# Sheet3.net
KiCad netlist of a schematic drawn in Altium Designer
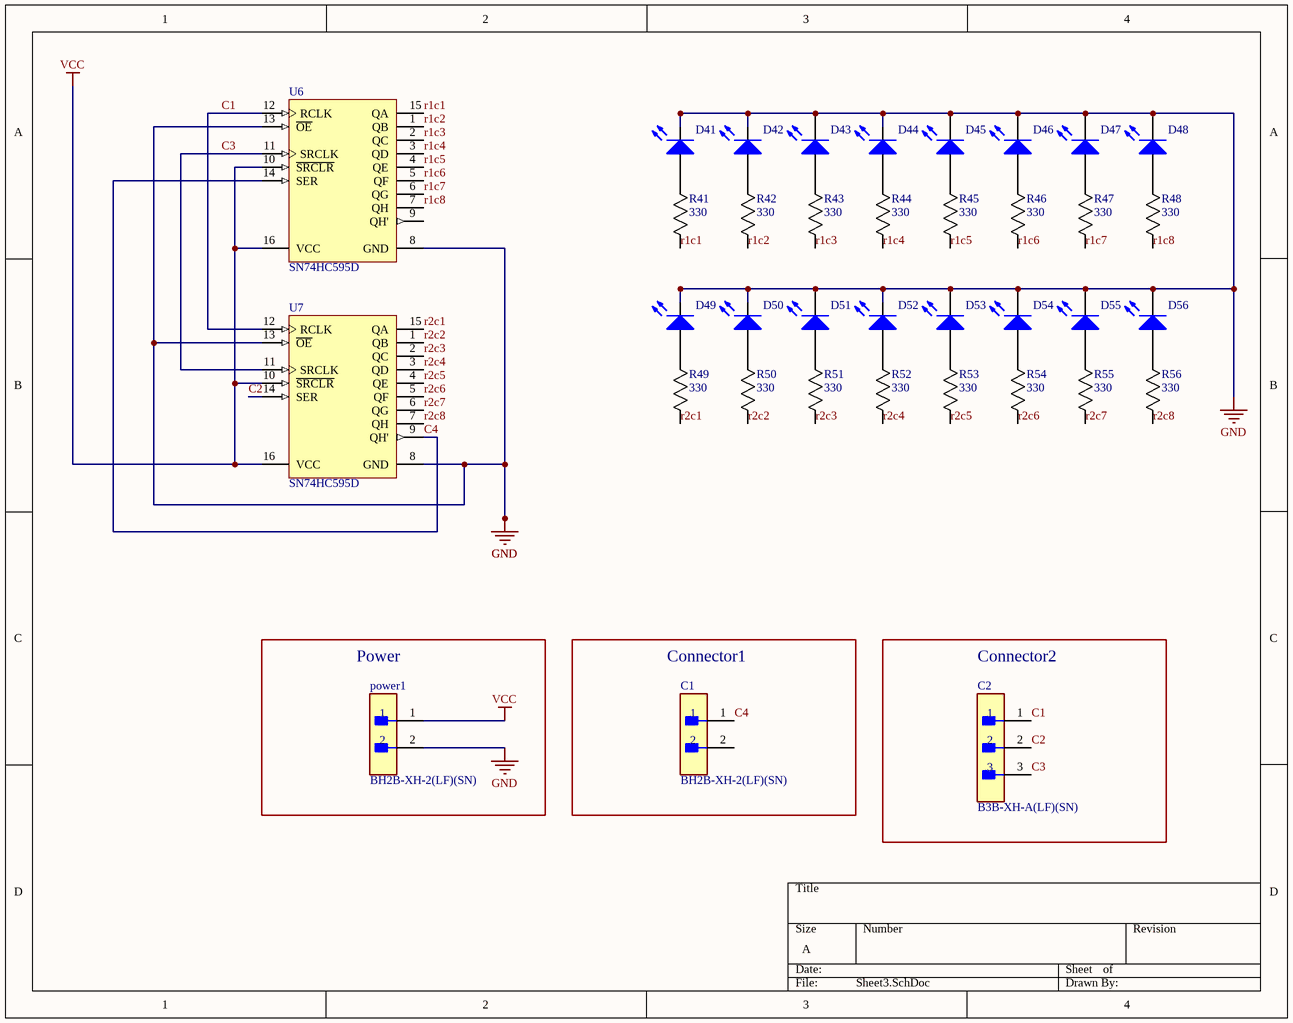
[diagram p0: Sheet3.SchDoc]

(export (version "E")
  (design (tool "Eeschema 10.0.6"))
  (components
    (comp (ref "C1")
      (value "BH2B-XH-2(LF)(SN)")
      (footprint "FP-BH2B-XH-2_LF_SN-MFG")
      (description "CONN HEADER VERT 2POS 2.5MM")
      (libsource (lib "Altium Content Vault") (part "3bc925449376181038e59eaffc5286c"))
    )
    (comp (ref "C2")
      (value "B3B-XH-A(LF)(SN)")
      (footprint "FP-B3B-XH-A_LF_SN-MFG")
      (description "CONN HEADER VERT 3POS 2.5MM")
      (libsource (lib "Altium Content Vault") (part "0d3f023dd272f625e17a2be33dea85f"))
    )
    (comp (ref "D41")
      (value "Light-Emitting Diode")
      (libsource (lib "Simulation Generic Components") (part "LED"))
    )
    (comp (ref "D42")
      (value "Light-Emitting Diode")
      (libsource (lib "Simulation Generic Components") (part "LED"))
    )
    (comp (ref "D43")
      (value "Light-Emitting Diode")
      (libsource (lib "Simulation Generic Components") (part "LED"))
    )
    (comp (ref "D44")
      (value "Light-Emitting Diode")
      (libsource (lib "Simulation Generic Components") (part "LED"))
    )
    (comp (ref "D45")
      (value "Light-Emitting Diode")
      (libsource (lib "Simulation Generic Components") (part "LED"))
    )
    (comp (ref "D46")
      (value "Light-Emitting Diode")
      (libsource (lib "Simulation Generic Components") (part "LED"))
    )
    (comp (ref "D47")
      (value "Light-Emitting Diode")
      (libsource (lib "Simulation Generic Components") (part "LED"))
    )
    (comp (ref "D48")
      (value "Light-Emitting Diode")
      (libsource (lib "Simulation Generic Components") (part "LED"))
    )
    (comp (ref "D49")
      (value "Light-Emitting Diode")
      (libsource (lib "Simulation Generic Components") (part "LED"))
    )
    (comp (ref "D50")
      (value "Light-Emitting Diode")
      (libsource (lib "Simulation Generic Components") (part "LED"))
    )
    (comp (ref "D51")
      (value "Light-Emitting Diode")
      (libsource (lib "Simulation Generic Components") (part "LED"))
    )
    (comp (ref "D52")
      (value "Light-Emitting Diode")
      (libsource (lib "Simulation Generic Components") (part "LED"))
    )
    (comp (ref "D53")
      (value "Light-Emitting Diode")
      (libsource (lib "Simulation Generic Components") (part "LED"))
    )
    (comp (ref "D54")
      (value "Light-Emitting Diode")
      (libsource (lib "Simulation Generic Components") (part "LED"))
    )
    (comp (ref "D55")
      (value "Light-Emitting Diode")
      (libsource (lib "Simulation Generic Components") (part "LED"))
    )
    (comp (ref "D56")
      (value "Light-Emitting Diode")
      (libsource (lib "Simulation Generic Components") (part "LED"))
    )
    (comp (ref "power1")
      (value "BH2B-XH-2(LF)(SN)")
      (footprint "FP-BH2B-XH-2_LF_SN-MFG")
      (description "CONN HEADER VERT 2POS 2.5MM")
      (libsource (lib "Altium Content Vault") (part "3bc925449376181038e59eaffc5286c"))
    )
    (comp (ref "R41")
      (value "330")
      (footprint "RES_AC03_VIS")
      (fields (field (name "TOLERANCE") "5%"))
      (libsource (lib "Altium Content Vault") (part "AC03000001000JAC00"))
    )
    (comp (ref "R42")
      (value "330")
      (footprint "RES_AC03_VIS")
      (fields (field (name "TOLERANCE") "5%"))
      (libsource (lib "Altium Content Vault") (part "AC03000001000JAC00"))
    )
    (comp (ref "R43")
      (value "330")
      (footprint "RES_AC03_VIS")
      (fields (field (name "TOLERANCE") "5%"))
      (libsource (lib "Altium Content Vault") (part "AC03000001000JAC00"))
    )
    (comp (ref "R44")
      (value "330")
      (footprint "RES_AC03_VIS")
      (fields (field (name "TOLERANCE") "5%"))
      (libsource (lib "Altium Content Vault") (part "AC03000001000JAC00"))
    )
    (comp (ref "R45")
      (value "330")
      (footprint "RES_AC03_VIS")
      (fields (field (name "TOLERANCE") "5%"))
      (libsource (lib "Altium Content Vault") (part "AC03000001000JAC00"))
    )
    (comp (ref "R46")
      (value "330")
      (footprint "RES_AC03_VIS")
      (fields (field (name "TOLERANCE") "5%"))
      (libsource (lib "Altium Content Vault") (part "AC03000001000JAC00"))
    )
    (comp (ref "R47")
      (value "330")
      (footprint "RES_AC03_VIS")
      (fields (field (name "TOLERANCE") "5%"))
      (libsource (lib "Altium Content Vault") (part "AC03000001000JAC00"))
    )
    (comp (ref "R48")
      (value "330")
      (footprint "RES_AC03_VIS")
      (fields (field (name "TOLERANCE") "5%"))
      (libsource (lib "Altium Content Vault") (part "AC03000001000JAC00"))
    )
    (comp (ref "R49")
      (value "330")
      (footprint "RES_AC03_VIS")
      (fields (field (name "TOLERANCE") "5%"))
      (libsource (lib "Altium Content Vault") (part "AC03000001000JAC00"))
    )
    (comp (ref "R50")
      (value "330")
      (footprint "RES_AC03_VIS")
      (fields (field (name "TOLERANCE") "5%"))
      (libsource (lib "Altium Content Vault") (part "AC03000001000JAC00"))
    )
    (comp (ref "R51")
      (value "330")
      (footprint "RES_AC03_VIS")
      (fields (field (name "TOLERANCE") "5%"))
      (libsource (lib "Altium Content Vault") (part "AC03000001000JAC00"))
    )
    (comp (ref "R52")
      (value "330")
      (footprint "RES_AC03_VIS")
      (fields (field (name "TOLERANCE") "5%"))
      (libsource (lib "Altium Content Vault") (part "AC03000001000JAC00"))
    )
    (comp (ref "R53")
      (value "330")
      (footprint "RES_AC03_VIS")
      (fields (field (name "TOLERANCE") "5%"))
      (libsource (lib "Altium Content Vault") (part "AC03000001000JAC00"))
    )
    (comp (ref "R54")
      (value "330")
      (footprint "RES_AC03_VIS")
      (fields (field (name "TOLERANCE") "5%"))
      (libsource (lib "Altium Content Vault") (part "AC03000001000JAC00"))
    )
    (comp (ref "R55")
      (value "330")
      (footprint "RES_AC03_VIS")
      (fields (field (name "TOLERANCE") "5%"))
      (libsource (lib "Altium Content Vault") (part "AC03000001000JAC00"))
    )
    (comp (ref "R56")
      (value "330")
      (footprint "RES_AC03_VIS")
      (fields (field (name "TOLERANCE") "5%"))
      (libsource (lib "Altium Content Vault") (part "AC03000001000JAC00"))
    )
    (comp (ref "U6")
      (value "SN74HC595D")
      (footprint "D0016A_L")
      (description "8-Bit Shift Registers With 3-State Output Registers, D0016A, TUBE")
      (fields
        (field (name "GENERIC PART NUMBER") "SN74HC595")
        (field (name "MANUFACTURER") "Texas Instruments")
      )
      (libsource (lib "Altium Content Vault") (part "TI-SN74XHCT595X_SN74LV595A-16"))
    )
    (comp (ref "U7")
      (value "SN74HC595D")
      (footprint "D0016A_L")
      (description "8-Bit Shift Registers With 3-State Output Registers, D0016A, TUBE")
      (fields
        (field (name "GENERIC PART NUMBER") "SN74HC595")
        (field (name "MANUFACTURER") "Texas Instruments")
      )
      (libsource (lib "Altium Content Vault") (part "TI-SN74XHCT595X_SN74LV595A-16"))
    )
  )
  (nets
    (net (code "1") (name "/C1") (class "Default")
      (node (ref "C2") (pin "1") (pinfunction "1_1") (pintype "passive"))
      (node (ref "U6") (pin "12") (pinfunction "RCLK_12") (pintype "input"))
      (node (ref "U7") (pin "12") (pinfunction "RCLK_12") (pintype "input"))
    )
    (net (code "2") (name "/C2") (class "Default")
      (node (ref "C2") (pin "2") (pinfunction "2_2") (pintype "passive"))
      (node (ref "U7") (pin "14") (pinfunction "SER_14") (pintype "input"))
    )
    (net (code "3") (name "/C3") (class "Default")
      (node (ref "C2") (pin "3") (pinfunction "3_3") (pintype "passive"))
      (node (ref "U6") (pin "11") (pinfunction "SRCLK_11") (pintype "input"))
      (node (ref "U7") (pin "11") (pinfunction "SRCLK_11") (pintype "input"))
    )
    (net (code "4") (name "/C4") (class "Default")
      (node (ref "C1") (pin "1") (pinfunction "1_1") (pintype "passive"))
      (node (ref "U6") (pin "14") (pinfunction "SER_14") (pintype "input"))
      (node (ref "U7") (pin "9") (pinfunction "QH'_9") (pintype "output"))
    )
    (net (code "5") (name "/r1c1") (class "Default")
      (node (ref "R41") (pin "1") (pinfunction "1_1") (pintype "passive"))
      (node (ref "U6") (pin "15") (pinfunction "QA_15") (pintype "tri_state"))
    )
    (net (code "6") (name "/r1c2") (class "Default")
      (node (ref "R42") (pin "1") (pinfunction "1_1") (pintype "passive"))
      (node (ref "U6") (pin "1") (pinfunction "QB_1") (pintype "tri_state"))
    )
    (net (code "7") (name "/r1c3") (class "Default")
      (node (ref "R43") (pin "1") (pinfunction "1_1") (pintype "passive"))
      (node (ref "U6") (pin "2") (pinfunction "QC_2") (pintype "tri_state"))
    )
    (net (code "8") (name "/r1c4") (class "Default")
      (node (ref "R44") (pin "1") (pinfunction "1_1") (pintype "passive"))
      (node (ref "U6") (pin "3") (pinfunction "QD_3") (pintype "tri_state"))
    )
    (net (code "9") (name "/r1c5") (class "Default")
      (node (ref "R45") (pin "1") (pinfunction "1_1") (pintype "passive"))
      (node (ref "U6") (pin "4") (pinfunction "QE_4") (pintype "tri_state"))
    )
    (net (code "10") (name "/r1c6") (class "Default")
      (node (ref "R46") (pin "1") (pinfunction "1_1") (pintype "passive"))
      (node (ref "U6") (pin "5") (pinfunction "QF_5") (pintype "tri_state"))
    )
    (net (code "11") (name "/r1c7") (class "Default")
      (node (ref "R47") (pin "1") (pinfunction "1_1") (pintype "passive"))
      (node (ref "U6") (pin "6") (pinfunction "QG_6") (pintype "tri_state"))
    )
    (net (code "12") (name "/r1c8") (class "Default")
      (node (ref "R48") (pin "1") (pinfunction "1_1") (pintype "passive"))
      (node (ref "U6") (pin "7") (pinfunction "QH_7") (pintype "tri_state"))
    )
    (net (code "13") (name "/r2c1") (class "Default")
      (node (ref "R49") (pin "1") (pinfunction "1_1") (pintype "passive"))
      (node (ref "U7") (pin "15") (pinfunction "QA_15") (pintype "tri_state"))
    )
    (net (code "14") (name "/r2c2") (class "Default")
      (node (ref "R50") (pin "1") (pinfunction "1_1") (pintype "passive"))
      (node (ref "U7") (pin "1") (pinfunction "QB_1") (pintype "tri_state"))
    )
    (net (code "15") (name "/r2c3") (class "Default")
      (node (ref "R51") (pin "1") (pinfunction "1_1") (pintype "passive"))
      (node (ref "U7") (pin "2") (pinfunction "QC_2") (pintype "tri_state"))
    )
    (net (code "16") (name "/r2c4") (class "Default")
      (node (ref "R52") (pin "1") (pinfunction "1_1") (pintype "passive"))
      (node (ref "U7") (pin "3") (pinfunction "QD_3") (pintype "tri_state"))
    )
    (net (code "17") (name "/r2c5") (class "Default")
      (node (ref "R53") (pin "1") (pinfunction "1_1") (pintype "passive"))
      (node (ref "U7") (pin "4") (pinfunction "QE_4") (pintype "tri_state"))
    )
    (net (code "18") (name "/r2c6") (class "Default")
      (node (ref "R54") (pin "1") (pinfunction "1_1") (pintype "passive"))
      (node (ref "U7") (pin "5") (pinfunction "QF_5") (pintype "tri_state"))
    )
    (net (code "19") (name "/r2c7") (class "Default")
      (node (ref "R55") (pin "1") (pinfunction "1_1") (pintype "passive"))
      (node (ref "U7") (pin "6") (pinfunction "QG_6") (pintype "tri_state"))
    )
    (net (code "20") (name "/r2c8") (class "Default")
      (node (ref "R56") (pin "1") (pinfunction "1_1") (pintype "passive"))
      (node (ref "U7") (pin "7") (pinfunction "QH_7") (pintype "tri_state"))
    )
    (net (code "21") (name "GND") (class "Default")
      (node (ref "D41") (pin "2") (pinfunction "K_2") (pintype "passive"))
      (node (ref "D42") (pin "2") (pinfunction "K_2") (pintype "passive"))
      (node (ref "D43") (pin "2") (pinfunction "K_2") (pintype "passive"))
      (node (ref "D44") (pin "2") (pinfunction "K_2") (pintype "passive"))
      (node (ref "D45") (pin "2") (pinfunction "K_2") (pintype "passive"))
      (node (ref "D46") (pin "2") (pinfunction "K_2") (pintype "passive"))
      (node (ref "D47") (pin "2") (pinfunction "K_2") (pintype "passive"))
      (node (ref "D48") (pin "2") (pinfunction "K_2") (pintype "passive"))
      (node (ref "D49") (pin "2") (pinfunction "K_2") (pintype "passive"))
      (node (ref "D50") (pin "2") (pinfunction "K_2") (pintype "passive"))
      (node (ref "D51") (pin "2") (pinfunction "K_2") (pintype "passive"))
      (node (ref "D52") (pin "2") (pinfunction "K_2") (pintype "passive"))
      (node (ref "D53") (pin "2") (pinfunction "K_2") (pintype "passive"))
      (node (ref "D54") (pin "2") (pinfunction "K_2") (pintype "passive"))
      (node (ref "D55") (pin "2") (pinfunction "K_2") (pintype "passive"))
      (node (ref "D56") (pin "2") (pinfunction "K_2") (pintype "passive"))
      (node (ref "U6") (pin "13") (pinfunction "~{OE}_13") (pintype "input"))
      (node (ref "U6") (pin "8") (pinfunction "GND_8") (pintype "power_in"))
      (node (ref "U7") (pin "13") (pinfunction "~{OE}_13") (pintype "input"))
      (node (ref "U7") (pin "8") (pinfunction "GND_8") (pintype "power_in"))
      (node (ref "power1") (pin "2") (pinfunction "2_2") (pintype "passive"))
    )
    (net (code "22") (name "Net-(D41-A)") (class "Default")
      (node (ref "D41") (pin "1") (pinfunction "A_1") (pintype "passive"))
      (node (ref "R41") (pin "2") (pinfunction "2_2") (pintype "passive"))
    )
    (net (code "23") (name "Net-(D42-A)") (class "Default")
      (node (ref "D42") (pin "1") (pinfunction "A_1") (pintype "passive"))
      (node (ref "R42") (pin "2") (pinfunction "2_2") (pintype "passive"))
    )
    (net (code "24") (name "Net-(D43-A)") (class "Default")
      (node (ref "D43") (pin "1") (pinfunction "A_1") (pintype "passive"))
      (node (ref "R43") (pin "2") (pinfunction "2_2") (pintype "passive"))
    )
    (net (code "25") (name "Net-(D44-A)") (class "Default")
      (node (ref "D44") (pin "1") (pinfunction "A_1") (pintype "passive"))
      (node (ref "R44") (pin "2") (pinfunction "2_2") (pintype "passive"))
    )
    (net (code "26") (name "Net-(D45-A)") (class "Default")
      (node (ref "D45") (pin "1") (pinfunction "A_1") (pintype "passive"))
      (node (ref "R45") (pin "2") (pinfunction "2_2") (pintype "passive"))
    )
    (net (code "27") (name "Net-(D46-A)") (class "Default")
      (node (ref "D46") (pin "1") (pinfunction "A_1") (pintype "passive"))
      (node (ref "R46") (pin "2") (pinfunction "2_2") (pintype "passive"))
    )
    (net (code "28") (name "Net-(D47-A)") (class "Default")
      (node (ref "D47") (pin "1") (pinfunction "A_1") (pintype "passive"))
      (node (ref "R47") (pin "2") (pinfunction "2_2") (pintype "passive"))
    )
    (net (code "29") (name "Net-(D48-A)") (class "Default")
      (node (ref "D48") (pin "1") (pinfunction "A_1") (pintype "passive"))
      (node (ref "R48") (pin "2") (pinfunction "2_2") (pintype "passive"))
    )
    (net (code "30") (name "Net-(D49-A)") (class "Default")
      (node (ref "D49") (pin "1") (pinfunction "A_1") (pintype "passive"))
      (node (ref "R49") (pin "2") (pinfunction "2_2") (pintype "passive"))
    )
    (net (code "31") (name "Net-(D50-A)") (class "Default")
      (node (ref "D50") (pin "1") (pinfunction "A_1") (pintype "passive"))
      (node (ref "R50") (pin "2") (pinfunction "2_2") (pintype "passive"))
    )
    (net (code "32") (name "Net-(D51-A)") (class "Default")
      (node (ref "D51") (pin "1") (pinfunction "A_1") (pintype "passive"))
      (node (ref "R51") (pin "2") (pinfunction "2_2") (pintype "passive"))
    )
    (net (code "33") (name "Net-(D52-A)") (class "Default")
      (node (ref "D52") (pin "1") (pinfunction "A_1") (pintype "passive"))
      (node (ref "R52") (pin "2") (pinfunction "2_2") (pintype "passive"))
    )
    (net (code "34") (name "Net-(D53-A)") (class "Default")
      (node (ref "D53") (pin "1") (pinfunction "A_1") (pintype "passive"))
      (node (ref "R53") (pin "2") (pinfunction "2_2") (pintype "passive"))
    )
    (net (code "35") (name "Net-(D54-A)") (class "Default")
      (node (ref "D54") (pin "1") (pinfunction "A_1") (pintype "passive"))
      (node (ref "R54") (pin "2") (pinfunction "2_2") (pintype "passive"))
    )
    (net (code "36") (name "Net-(D55-A)") (class "Default")
      (node (ref "D55") (pin "1") (pinfunction "A_1") (pintype "passive"))
      (node (ref "R55") (pin "2") (pinfunction "2_2") (pintype "passive"))
    )
    (net (code "37") (name "Net-(D56-A)") (class "Default")
      (node (ref "D56") (pin "1") (pinfunction "A_1") (pintype "passive"))
      (node (ref "R56") (pin "2") (pinfunction "2_2") (pintype "passive"))
    )
    (net (code "38") (name "VCC") (class "Default")
      (node (ref "U6") (pin "10") (pinfunction "~{SRCLR}_10") (pintype "input"))
      (node (ref "U6") (pin "16") (pinfunction "VCC_16") (pintype "power_in"))
      (node (ref "U7") (pin "10") (pinfunction "~{SRCLR}_10") (pintype "input"))
      (node (ref "U7") (pin "16") (pinfunction "VCC_16") (pintype "power_in"))
      (node (ref "power1") (pin "1") (pinfunction "1_1") (pintype "passive"))
    )
    (net (code "39") (name "unconnected-(C1-Pad2)") (class "Default")
      (node (ref "C1") (pin "2") (pinfunction "2_2") (pintype "passive"))
    )
    (net (code "40") (name "unconnected-(U6-QH'-Pad9)") (class "Default")
      (node (ref "U6") (pin "9") (pinfunction "QH'_9") (pintype "output"))
    )
  )
)
